# STM3205P_Controller.net
KiCad netlist of a schematic drawn in Altium Designer
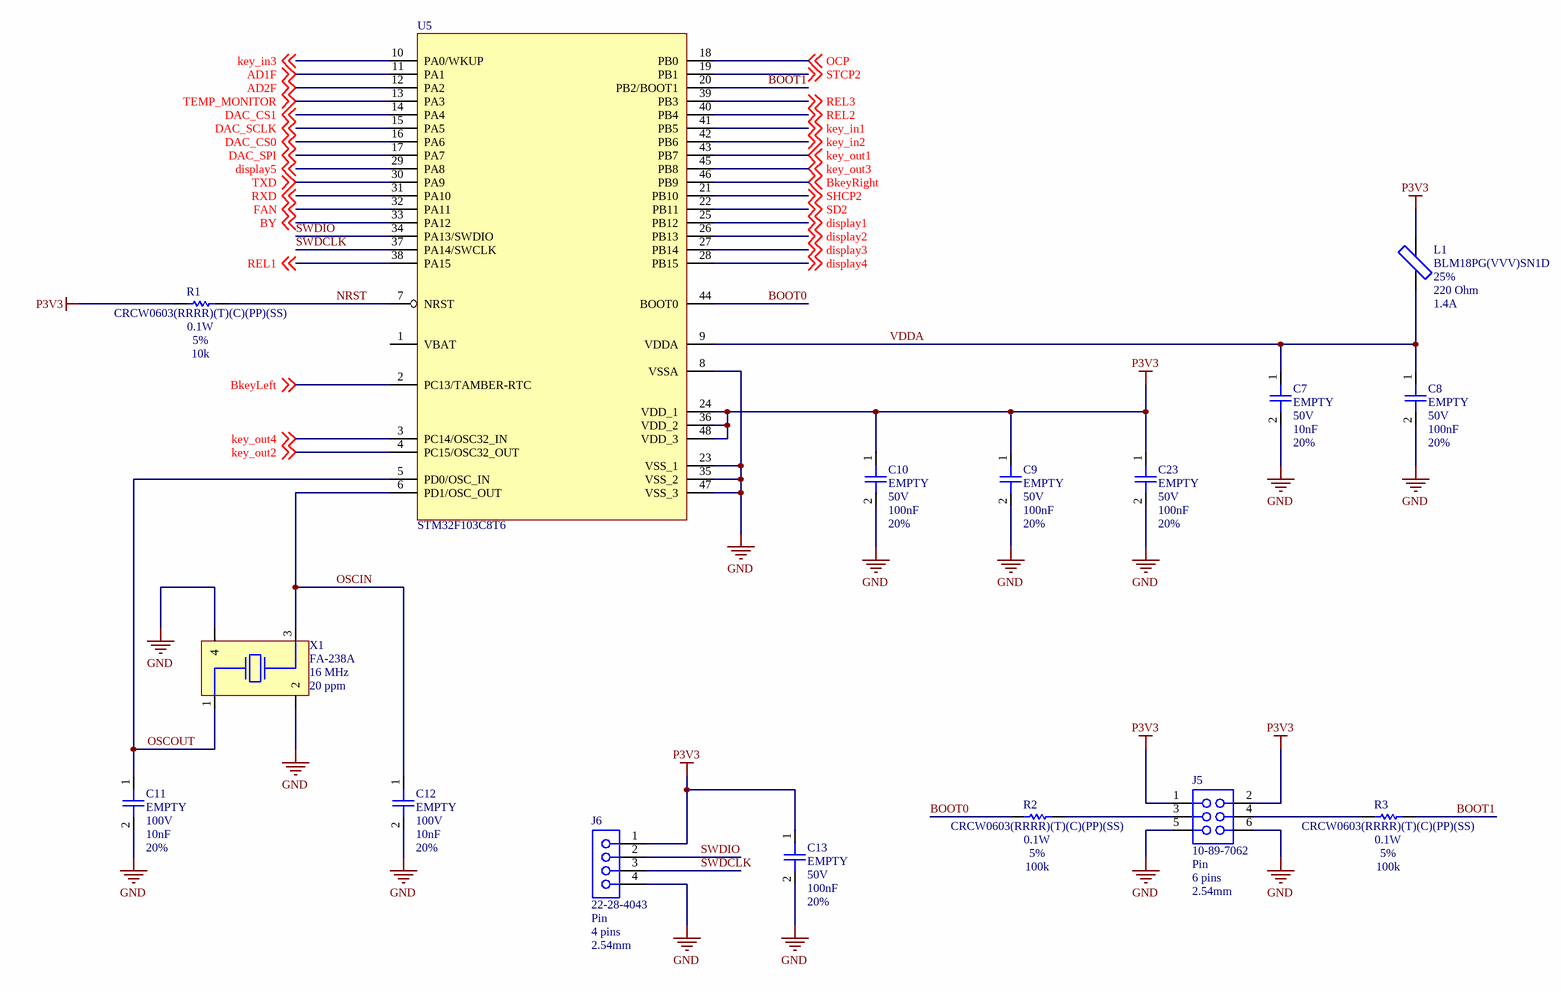
[diagram p0: STM3205P_Controller.SchDoc]

(export (version "E")
  (design (tool "Eeschema 10.0.6"))
  (components
    (comp (ref "C7")
      (value "10nF")
      (footprint "CAP0603")
      (description "Surface Mount Multilayer Ceramic Chip Capacitors  for Commercial Applications")
      (fields
        (field (name "PARTNUMBER1") "EMPTY")
        (field (name "VOLTAGE") "50V")
        (field (name "TOLERANCE") "20%")
        (field (name "Comment") "CC0603")
        (field (name "PUBLISHER") "Lucas Moraes")
      )
      (libsource (lib "CeramicCapacitors") (part "CC0603"))
    )
    (comp (ref "C8")
      (value "100nF")
      (footprint "CAP0603")
      (description "Surface Mount Multilayer Ceramic Chip Capacitors  for Commercial Applications")
      (fields
        (field (name "PARTNUMBER1") "EMPTY")
        (field (name "VOLTAGE") "50V")
        (field (name "TOLERANCE") "20%")
        (field (name "Comment") "CC0603")
        (field (name "PUBLISHER") "Lucas Moraes")
      )
      (libsource (lib "CeramicCapacitors") (part "CC0603"))
    )
    (comp (ref "C9")
      (value "100nF")
      (footprint "CAP0603")
      (description "Surface Mount Multilayer Ceramic Chip Capacitors  for Commercial Applications")
      (fields
        (field (name "PARTNUMBER1") "EMPTY")
        (field (name "VOLTAGE") "50V")
        (field (name "TOLERANCE") "20%")
        (field (name "Comment") "CC0603")
        (field (name "PUBLISHER") "Lucas Moraes")
      )
      (libsource (lib "CeramicCapacitors") (part "CC0603"))
    )
    (comp (ref "C10")
      (value "100nF")
      (footprint "CAP0603")
      (description "Surface Mount Multilayer Ceramic Chip Capacitors  for Commercial Applications")
      (fields
        (field (name "PARTNUMBER1") "EMPTY")
        (field (name "VOLTAGE") "50V")
        (field (name "TOLERANCE") "20%")
        (field (name "Comment") "CC0603")
        (field (name "PUBLISHER") "Lucas Moraes")
      )
      (libsource (lib "CeramicCapacitors") (part "CC0603"))
    )
    (comp (ref "C11")
      (value "10nF")
      (footprint "CAP0603")
      (description "Surface Mount Multilayer Ceramic Chip Capacitors  for Commercial Applications")
      (fields
        (field (name "PARTNUMBER1") "EMPTY")
        (field (name "VOLTAGE") "100V")
        (field (name "TOLERANCE") "20%")
        (field (name "Comment") "CC0603")
        (field (name "PUBLISHER") "Lucas Moraes")
      )
      (libsource (lib "CeramicCapacitors") (part "CC0603"))
    )
    (comp (ref "C12")
      (value "10nF")
      (footprint "CAP0603")
      (description "Surface Mount Multilayer Ceramic Chip Capacitors  for Commercial Applications")
      (fields
        (field (name "PARTNUMBER1") "EMPTY")
        (field (name "VOLTAGE") "100V")
        (field (name "TOLERANCE") "20%")
        (field (name "Comment") "CC0603")
        (field (name "PUBLISHER") "Lucas Moraes")
      )
      (libsource (lib "CeramicCapacitors") (part "CC0603"))
    )
    (comp (ref "C13")
      (value "100nF")
      (footprint "CAP0603")
      (description "Surface Mount Multilayer Ceramic Chip Capacitors  for Commercial Applications")
      (fields
        (field (name "PARTNUMBER1") "EMPTY")
        (field (name "VOLTAGE") "50V")
        (field (name "TOLERANCE") "20%")
        (field (name "Comment") "CC0603")
        (field (name "PUBLISHER") "Lucas Moraes")
      )
      (libsource (lib "CeramicCapacitors") (part "CC0603"))
    )
    (comp (ref "C23")
      (value "100nF")
      (footprint "CAP0603")
      (description "Surface Mount Multilayer Ceramic Chip Capacitors  for Commercial Applications")
      (fields
        (field (name "PARTNUMBER1") "EMPTY")
        (field (name "VOLTAGE") "50V")
        (field (name "TOLERANCE") "20%")
        (field (name "Comment") "CC0603")
        (field (name "PUBLISHER") "Lucas Moraes")
      )
      (libsource (lib "CeramicCapacitors") (part "CC0603"))
    )
    (comp (ref "J5")
      (value "10-89-7062")
      (footprint "CONDIL06STRMALE_100_100")
      (description "Headers & Wire Housings C-Grid PCB Conn SR V onn SR Vt Tn-A 8Ckt")
      (fields
        (field (name "PARTNUMBER1") "10-89-7062")
        (field (name "TYPE") "Pin")
        (field (name "PINS") "6 pins")
        (field (name "PITCH") "2.54mm")
        (field (name "PUBLISHER") "Lucas Moraes")
      )
      (libsource (lib "HeaderPin") (part "10-89-7062"))
    )
    (comp (ref "J6")
      (value "22-28-4043")
      (footprint "CONSIL04STRMALE_100_100")
      (description "Headers & Wire Housings 04 MODII HDR SRST B/A .100CL")
      (fields
        (field (name "PARTNUMBER1") "22-28-4043")
        (field (name "TYPE") "Pin")
        (field (name "PINS") "4 pins")
        (field (name "PITCH") "2.54mm")
        (field (name "PUBLISHER") "Lucas Moraes")
      )
      (libsource (lib "HeaderPin") (part "22-28-4043"))
    )
    (comp (ref "L1")
      (value "220 Ohm")
      (footprint "IND0603")
      (description "Ferrite Beads 0603")
      (fields
        (field (name "PARTNUMBER1") "BLM18PG(VVV)SN1D")
        (field (name "TOLERANCE") "25%")
        (field (name "CURRENT") "1.4A")
        (field (name "Comment") "BLM18")
        (field (name "PUBLISHER") "Lucas Moraes")
      )
      (libsource (lib "Inductor") (part "BLM18"))
    )
    (comp (ref "R1")
      (value "10k")
      (footprint "RES0603")
      (description "Thick Film Chip Resistors with CECC Approval,  available with Established Reliability")
      (fields
        (field (name "PARTNUMBER1") "CRCW0603(RRRR)(T)(C)(PP)(SS)")
        (field (name "POWER") "0.1W")
        (field (name "TOLERANCE") "5%")
        (field (name "Comment") "Chip Resistor")
        (field (name "PUBLISHER") "Lucas Moraes")
      )
      (libsource (lib "ResistorsFixed") (part "CRCW0603"))
    )
    (comp (ref "R2")
      (value "100k")
      (footprint "RES0603")
      (description "Thick Film Chip Resistors with CECC Approval,  available with Established Reliability")
      (fields
        (field (name "PARTNUMBER1") "CRCW0603(RRRR)(T)(C)(PP)(SS)")
        (field (name "POWER") "0.1W")
        (field (name "TOLERANCE") "5%")
        (field (name "Comment") "Chip Resistor")
        (field (name "PUBLISHER") "Lucas Moraes")
      )
      (libsource (lib "ResistorsFixed") (part "CRCW0603"))
    )
    (comp (ref "R3")
      (value "100k")
      (footprint "RES0603")
      (description "Thick Film Chip Resistors with CECC Approval,  available with Established Reliability")
      (fields
        (field (name "PARTNUMBER1") "CRCW0603(RRRR)(T)(C)(PP)(SS)")
        (field (name "POWER") "0.1W")
        (field (name "TOLERANCE") "5%")
        (field (name "Comment") "Chip Resistor")
        (field (name "PUBLISHER") "Lucas Moraes")
      )
      (libsource (lib "ResistorsFixed") (part "CRCW0603"))
    )
    (comp (ref "U5")
      (value "STM32F103C8T6")
      (footprint "LQFP-48")
      (description "32-bit Microcontrollers - ARM Cortex-M0+ 32kB Flash, 6kB RAM")
      (fields (field (name "PARTNUMBER1") "STM32F103C8T6") (field (name "PUBLISHER") "Lucas Moraes"))
      (libsource (lib "STM32Microcontrollers") (part "STM32F103C8T6"))
    )
    (comp (ref "X1")
      (value "16 MHz")
      (footprint "CR3225")
      (description "Crystals FA-238A XTAL MHZ -40 125C 7.0PF 250TR")
      (fields
        (field (name "PARTNUMBER1") "FA-238A")
        (field (name "TOLERANCE") "20 ppm")
        (field (name "Comment") "FA-238A")
        (field (name "PUBLISHER") "Lucas Moraes")
      )
      (libsource (lib "Crystals") (part "FA-238A"))
    )
  )
  (nets
    (net (code "1") (name "/BOOT0") (class "Default")
      (node (ref "R2") (pin "1") (pinfunction "1_1") (pintype "passive"))
      (node (ref "U5") (pin "44") (pinfunction "BOOT0_44") (pintype "passive"))
    )
    (net (code "2") (name "/BOOT1") (class "Default")
      (node (ref "R3") (pin "2") (pinfunction "2_2") (pintype "passive"))
      (node (ref "U5") (pin "20") (pinfunction "PB2/BOOT1_20") (pintype "passive"))
    )
    (net (code "3") (name "/NRST") (class "Default")
      (node (ref "R1") (pin "2") (pinfunction "2_2") (pintype "passive"))
      (node (ref "U5") (pin "7") (pinfunction "NRST_7") (pintype "passive"))
    )
    (net (code "4") (name "/OSCIN") (class "Default")
      (node (ref "C12") (pin "1") (pinfunction "1_1") (pintype "passive"))
      (node (ref "U5") (pin "6") (pinfunction "PD1/OSC_OUT_6") (pintype "passive"))
      (node (ref "X1") (pin "3") (pinfunction "3_3") (pintype "passive"))
    )
    (net (code "5") (name "/OSCOUT") (class "Default")
      (node (ref "C11") (pin "1") (pinfunction "1_1") (pintype "passive"))
      (node (ref "U5") (pin "5") (pinfunction "PD0/OSC_IN_5") (pintype "passive"))
      (node (ref "X1") (pin "1") (pinfunction "1_1") (pintype "passive"))
    )
    (net (code "6") (name "/SWDCLK") (class "Default")
      (node (ref "J6") (pin "3") (pinfunction "3_3") (pintype "passive"))
      (node (ref "U5") (pin "37") (pinfunction "PA14/SWCLK_37") (pintype "passive"))
    )
    (net (code "7") (name "/SWDIO") (class "Default")
      (node (ref "J6") (pin "2") (pinfunction "2_2") (pintype "passive"))
      (node (ref "U5") (pin "34") (pinfunction "PA13/SWDIO_34") (pintype "passive"))
    )
    (net (code "8") (name "/VDDA") (class "Default")
      (node (ref "C7") (pin "1") (pinfunction "1_1") (pintype "passive"))
      (node (ref "C8") (pin "1") (pinfunction "1_1") (pintype "passive"))
      (node (ref "L1") (pin "1") (pinfunction "1_1") (pintype "passive"))
      (node (ref "U5") (pin "9") (pinfunction "VDDA_9") (pintype "power_in"))
    )
    (net (code "9") (name "AD1F") (class "Default")
      (node (ref "U5") (pin "11") (pinfunction "PA1_11") (pintype "passive"))
    )
    (net (code "10") (name "AD2F") (class "Default")
      (node (ref "U5") (pin "12") (pinfunction "PA2_12") (pintype "passive"))
    )
    (net (code "11") (name "BY") (class "Default")
      (node (ref "U5") (pin "33") (pinfunction "PA12_33") (pintype "passive"))
    )
    (net (code "12") (name "BkeyLeft") (class "Default")
      (node (ref "U5") (pin "2") (pinfunction "PC13/TAMBER-RTC_2") (pintype "passive"))
    )
    (net (code "13") (name "BkeyRight") (class "Default")
      (node (ref "U5") (pin "46") (pinfunction "PB9_46") (pintype "passive"))
    )
    (net (code "14") (name "DAC_CS0") (class "Default")
      (node (ref "U5") (pin "16") (pinfunction "PA6_16") (pintype "passive"))
    )
    (net (code "15") (name "DAC_CS1") (class "Default")
      (node (ref "U5") (pin "14") (pinfunction "PA4_14") (pintype "passive"))
    )
    (net (code "16") (name "DAC_SCLK") (class "Default")
      (node (ref "U5") (pin "15") (pinfunction "PA5_15") (pintype "passive"))
    )
    (net (code "17") (name "DAC_SPI") (class "Default")
      (node (ref "U5") (pin "17") (pinfunction "PA7_17") (pintype "passive"))
    )
    (net (code "18") (name "FAN") (class "Default")
      (node (ref "U5") (pin "32") (pinfunction "PA11_32") (pintype "passive"))
    )
    (net (code "19") (name "GND") (class "Default")
      (node (ref "C10") (pin "2") (pinfunction "2_2") (pintype "passive"))
      (node (ref "C11") (pin "2") (pinfunction "2_2") (pintype "passive"))
      (node (ref "C12") (pin "2") (pinfunction "2_2") (pintype "passive"))
      (node (ref "C13") (pin "2") (pinfunction "2_2") (pintype "passive"))
      (node (ref "C23") (pin "2") (pinfunction "2_2") (pintype "passive"))
      (node (ref "C7") (pin "2") (pinfunction "2_2") (pintype "passive"))
      (node (ref "C8") (pin "2") (pinfunction "2_2") (pintype "passive"))
      (node (ref "C9") (pin "2") (pinfunction "2_2") (pintype "passive"))
      (node (ref "J5") (pin "5") (pinfunction "5_5") (pintype "passive"))
      (node (ref "J5") (pin "6") (pinfunction "6_6") (pintype "passive"))
      (node (ref "J6") (pin "4") (pinfunction "4_4") (pintype "passive"))
      (node (ref "U5") (pin "23") (pinfunction "VSS_1_23") (pintype "power_in"))
      (node (ref "U5") (pin "35") (pinfunction "VSS_2_35") (pintype "power_in"))
      (node (ref "U5") (pin "47") (pinfunction "VSS_3_47") (pintype "power_in"))
      (node (ref "U5") (pin "8") (pinfunction "VSSA_8") (pintype "power_in"))
      (node (ref "X1") (pin "2") (pinfunction "2_2") (pintype "passive"))
      (node (ref "X1") (pin "4") (pinfunction "4_4") (pintype "passive"))
    )
    (net (code "20") (name "Net-(J5-Pad3)") (class "Default")
      (node (ref "J5") (pin "3") (pinfunction "3_3") (pintype "passive"))
      (node (ref "R2") (pin "2") (pinfunction "2_2") (pintype "passive"))
    )
    (net (code "21") (name "Net-(J5-Pad4)") (class "Default")
      (node (ref "J5") (pin "4") (pinfunction "4_4") (pintype "passive"))
      (node (ref "R3") (pin "1") (pinfunction "1_1") (pintype "passive"))
    )
    (net (code "22") (name "OCP") (class "Default")
      (node (ref "U5") (pin "18") (pinfunction "PB0_18") (pintype "passive"))
    )
    (net (code "23") (name "P3V3") (class "Default")
      (node (ref "C10") (pin "1") (pinfunction "1_1") (pintype "passive"))
      (node (ref "C13") (pin "1") (pinfunction "1_1") (pintype "passive"))
      (node (ref "C23") (pin "1") (pinfunction "1_1") (pintype "passive"))
      (node (ref "C9") (pin "1") (pinfunction "1_1") (pintype "passive"))
      (node (ref "J5") (pin "1") (pinfunction "1_1") (pintype "passive"))
      (node (ref "J5") (pin "2") (pinfunction "2_2") (pintype "passive"))
      (node (ref "J6") (pin "1") (pinfunction "1_1") (pintype "passive"))
      (node (ref "L1") (pin "2") (pinfunction "2_2") (pintype "passive"))
      (node (ref "R1") (pin "1") (pinfunction "1_1") (pintype "passive"))
      (node (ref "U5") (pin "24") (pinfunction "VDD_1_24") (pintype "power_in"))
      (node (ref "U5") (pin "36") (pinfunction "VDD_2_36") (pintype "power_in"))
      (node (ref "U5") (pin "48") (pinfunction "VDD_3_48") (pintype "power_in"))
    )
    (net (code "24") (name "REL1") (class "Default")
      (node (ref "U5") (pin "38") (pinfunction "PA15_38") (pintype "passive"))
    )
    (net (code "25") (name "REL2") (class "Default")
      (node (ref "U5") (pin "40") (pinfunction "PB4_40") (pintype "passive"))
    )
    (net (code "26") (name "REL3") (class "Default")
      (node (ref "U5") (pin "39") (pinfunction "PB3_39") (pintype "passive"))
    )
    (net (code "27") (name "RXD") (class "Default")
      (node (ref "U5") (pin "31") (pinfunction "PA10_31") (pintype "passive"))
    )
    (net (code "28") (name "SD2") (class "Default")
      (node (ref "U5") (pin "22") (pinfunction "PB11_22") (pintype "passive"))
    )
    (net (code "29") (name "SHCP2") (class "Default")
      (node (ref "U5") (pin "21") (pinfunction "PB10_21") (pintype "passive"))
    )
    (net (code "30") (name "STCP2") (class "Default")
      (node (ref "U5") (pin "19") (pinfunction "PB1_19") (pintype "passive"))
    )
    (net (code "31") (name "TEMP_MONITOR") (class "Default")
      (node (ref "U5") (pin "13") (pinfunction "PA3_13") (pintype "passive"))
    )
    (net (code "32") (name "TXD") (class "Default")
      (node (ref "U5") (pin "30") (pinfunction "PA9_30") (pintype "passive"))
    )
    (net (code "33") (name "display1") (class "Default")
      (node (ref "U5") (pin "25") (pinfunction "PB12_25") (pintype "passive"))
    )
    (net (code "34") (name "display2") (class "Default")
      (node (ref "U5") (pin "26") (pinfunction "PB13_26") (pintype "passive"))
    )
    (net (code "35") (name "display3") (class "Default")
      (node (ref "U5") (pin "27") (pinfunction "PB14_27") (pintype "passive"))
    )
    (net (code "36") (name "display4") (class "Default")
      (node (ref "U5") (pin "28") (pinfunction "PB15_28") (pintype "passive"))
    )
    (net (code "37") (name "display5") (class "Default")
      (node (ref "U5") (pin "29") (pinfunction "PA8_29") (pintype "passive"))
    )
    (net (code "38") (name "key_in1") (class "Default")
      (node (ref "U5") (pin "41") (pinfunction "PB5_41") (pintype "passive"))
    )
    (net (code "39") (name "key_in2") (class "Default")
      (node (ref "U5") (pin "42") (pinfunction "PB6_42") (pintype "passive"))
    )
    (net (code "40") (name "key_in3") (class "Default")
      (node (ref "U5") (pin "10") (pinfunction "PA0/WKUP_10") (pintype "passive"))
    )
    (net (code "41") (name "key_out1") (class "Default")
      (node (ref "U5") (pin "43") (pinfunction "PB7_43") (pintype "passive"))
    )
    (net (code "42") (name "key_out2") (class "Default")
      (node (ref "U5") (pin "4") (pinfunction "PC15/OSC32_OUT_4") (pintype "passive"))
    )
    (net (code "43") (name "key_out3") (class "Default")
      (node (ref "U5") (pin "45") (pinfunction "PB8_45") (pintype "passive"))
    )
    (net (code "44") (name "key_out4") (class "Default")
      (node (ref "U5") (pin "3") (pinfunction "PC14/OSC32_IN_3") (pintype "passive"))
    )
    (net (code "45") (name "unconnected-(U5-VBAT-Pad1)") (class "Default")
      (node (ref "U5") (pin "1") (pinfunction "VBAT_1") (pintype "passive"))
    )
  )
)
